# QR_Scanning1_V1_STM32.net
KiCad netlist of a schematic drawn in Altium Designer
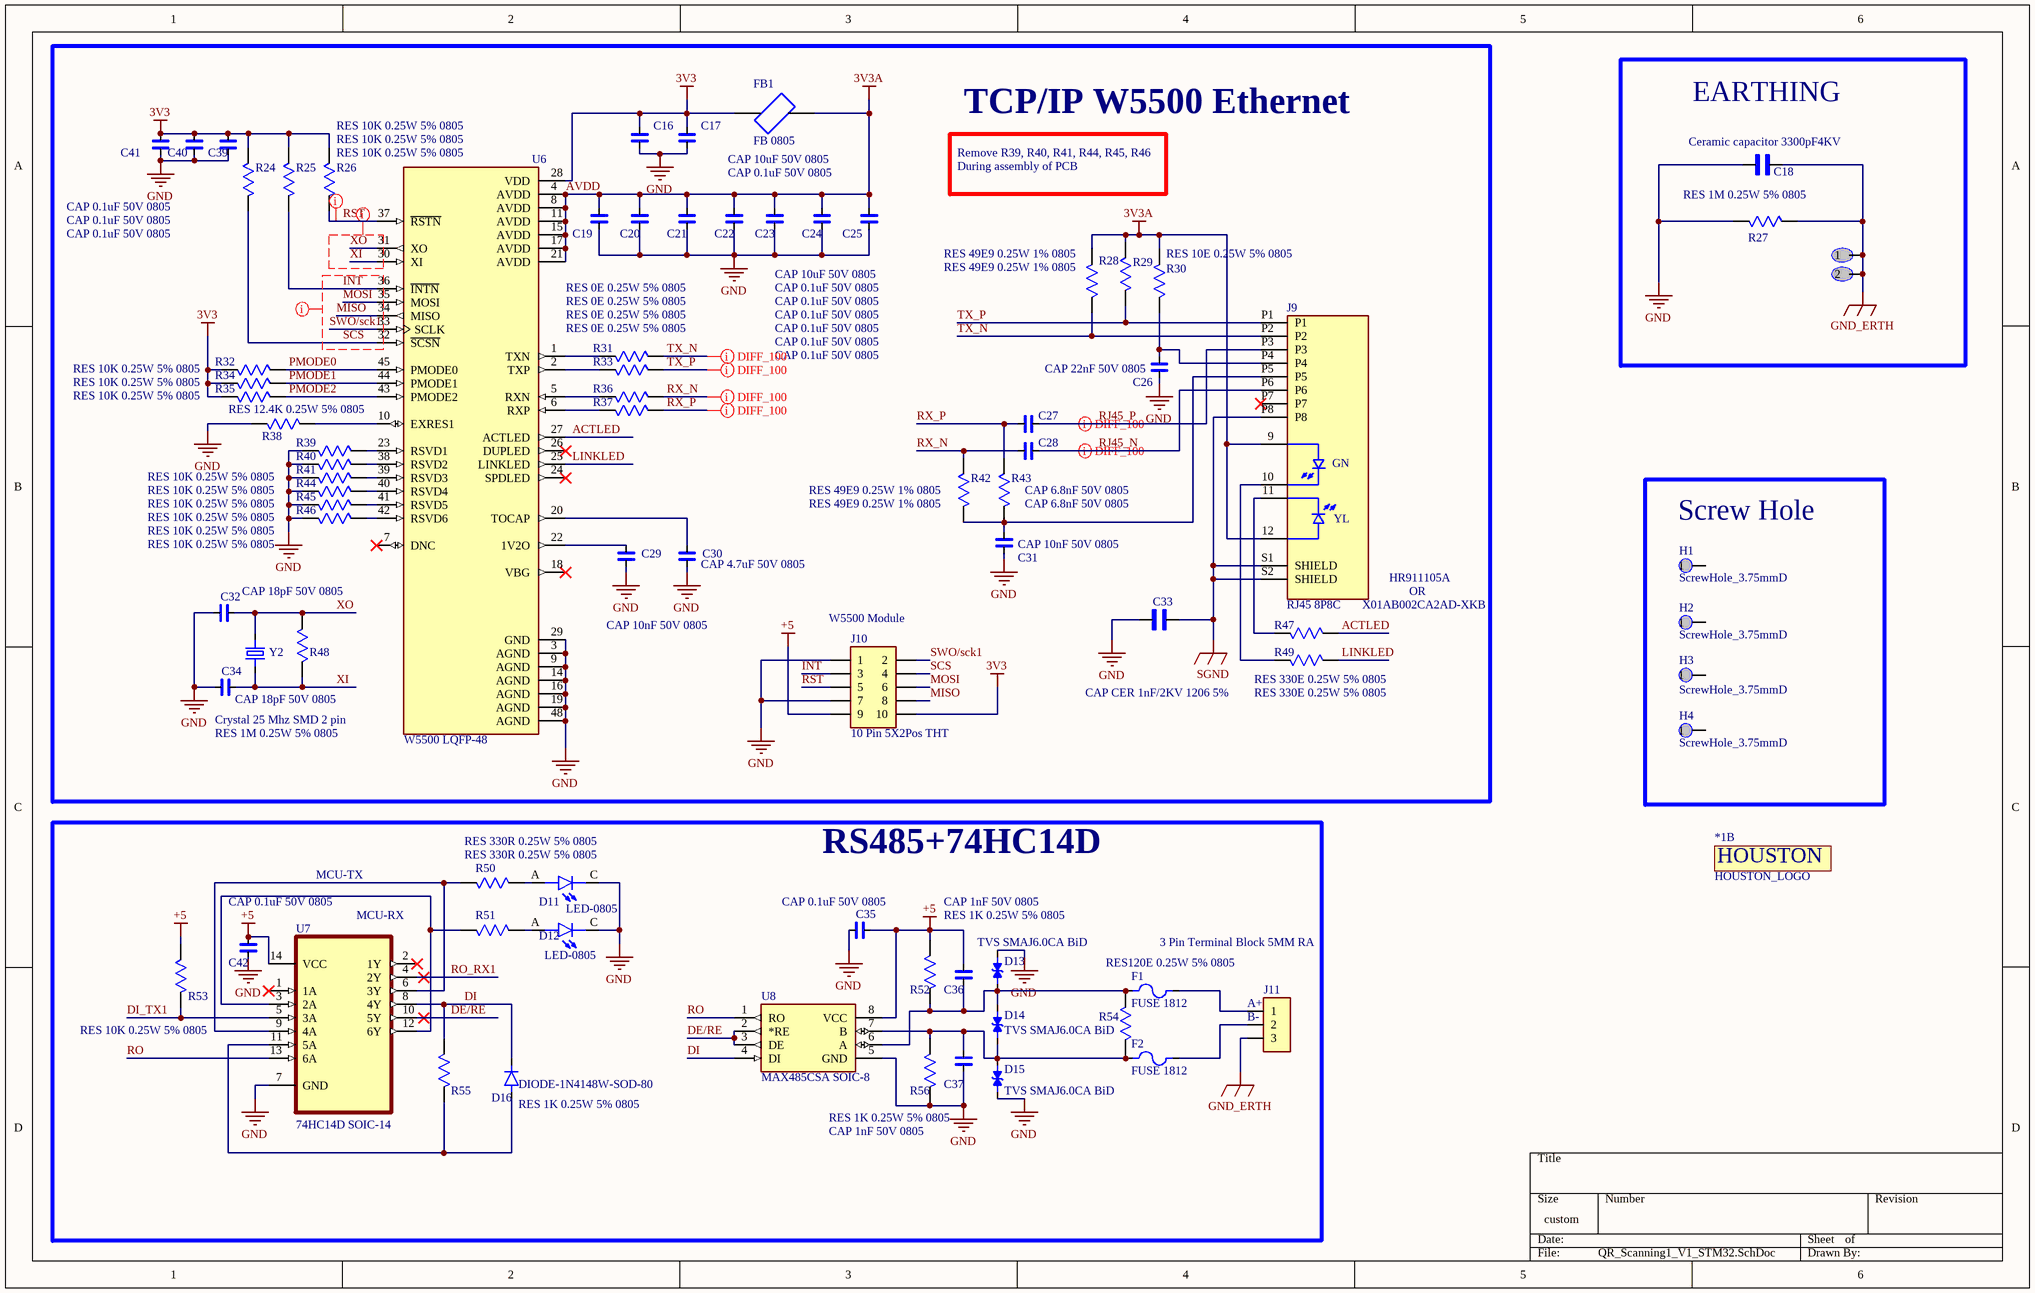
[diagram p0: QR_Scanning1_V1_STM32.SchDoc]

(export (version "E")
  (design (tool "Eeschema 10.0.6"))
  (components
    (comp (ref "*1")
      (value "HOUSTON_LOGO")
      (footprint "HOUSTON_LOGO")
      (libsource (lib "PGS") (part "HOUSTON_LOGO"))
    )
    (comp (ref "C16")
      (value "CAP 0.1uF 50V 0805")
      (footprint "CAP CER 0.1uF/50V 5%")
      (description "CAP CER 0.1uF/50V  Ceramic Capacitor X7R 0805 (2012 Metric) SMT")
      (fields (field (name "MF") "Samsung") (field (name "MP") "CL21B104KCFNNNE"))
      (libsource (lib "Ticket Scanning") (part "CAP CER 0.1uF/50V 5%"))
    )
    (comp (ref "C17")
      (value "CAP 10uF 50V 0805")
      (footprint "CAP CER 0.1uF/50V 5%")
      (description "CAP CER 0.1uF/50V  Ceramic Capacitor X7R 0805 (2012 Metric) SMT")
      (fields (field (name "MF") "Samsung") (field (name "MP") "CL21B104KCFNNNE"))
      (libsource (lib "Ticket Scanning") (part "CAP CER 0.1uF/50V 5%"))
    )
    (comp (ref "C18")
      (value "Ceramic capacitor 3300pF4KV")
      (footprint "Ceramic capacitor 3300pF4KV")
      (description "Ceramic capacitor 3300pF4KV, Tension nominale 400Vac(r.m.s.), 4KV ESD, DE2E3SA332MA3BY02F")
      (fields (field (name "MF") "Murata") (field (name "MP") "DE2E3SA332MA3BY02F"))
      (libsource (lib "Ticket Scanning") (part "Ceramic capacitor 3300pF4KV"))
    )
    (comp (ref "C19")
      (value "CAP 0.1uF 50V 0805")
      (footprint "CAP CER 0.1uF/50V 5%")
      (description "CAP CER 0.1uF/50V  Ceramic Capacitor X7R 0805 (2012 Metric) SMT")
      (fields (field (name "MF") "Samsung") (field (name "MP") "CL21B104KCFNNNE"))
      (libsource (lib "Ticket Scanning") (part "CAP CER 0.1uF/50V 5%"))
    )
    (comp (ref "C20")
      (value "CAP 0.1uF 50V 0805")
      (footprint "CAP CER 0.1uF/50V 5%")
      (description "CAP CER 0.1uF/50V  Ceramic Capacitor X7R 0805 (2012 Metric) SMT")
      (fields (field (name "MF") "Samsung") (field (name "MP") "CL21B104KCFNNNE"))
      (libsource (lib "Ticket Scanning") (part "CAP CER 0.1uF/50V 5%"))
    )
    (comp (ref "C21")
      (value "CAP 0.1uF 50V 0805")
      (footprint "CAP CER 0.1uF/50V 5%")
      (description "CAP CER 0.1uF/50V  Ceramic Capacitor X7R 0805 (2012 Metric) SMT")
      (fields (field (name "MF") "Samsung") (field (name "MP") "CL21B104KCFNNNE"))
      (libsource (lib "Ticket Scanning") (part "CAP CER 0.1uF/50V 5%"))
    )
    (comp (ref "C22")
      (value "CAP 0.1uF 50V 0805")
      (footprint "CAP CER 0.1uF/50V 5%")
      (description "CAP CER 0.1uF/50V  Ceramic Capacitor X7R 0805 (2012 Metric) SMT")
      (fields (field (name "MF") "Samsung") (field (name "MP") "CL21B104KCFNNNE"))
      (libsource (lib "Ticket Scanning") (part "CAP CER 0.1uF/50V 5%"))
    )
    (comp (ref "C23")
      (value "CAP 0.1uF 50V 0805")
      (footprint "CAP CER 0.1uF/50V 5%")
      (description "CAP CER 0.1uF/50V  Ceramic Capacitor X7R 0805 (2012 Metric) SMT")
      (fields (field (name "MF") "Samsung") (field (name "MP") "CL21B104KCFNNNE"))
      (libsource (lib "Ticket Scanning") (part "CAP CER 0.1uF/50V 5%"))
    )
    (comp (ref "C24")
      (value "CAP 0.1uF 50V 0805")
      (footprint "CAP CER 0.1uF/50V 5%")
      (description "CAP CER 0.1uF/50V  Ceramic Capacitor X7R 0805 (2012 Metric) SMT")
      (fields (field (name "MF") "Samsung") (field (name "MP") "CL21B104KCFNNNE"))
      (libsource (lib "Ticket Scanning") (part "CAP CER 0.1uF/50V 5%"))
    )
    (comp (ref "C25")
      (value "CAP 10uF 50V 0805")
      (footprint "CAP CER 0.1uF/50V 5%")
      (description "CAP CER 0.1uF/50V  Ceramic Capacitor X7R 0805 (2012 Metric) SMT")
      (fields (field (name "MF") "Samsung") (field (name "MP") "CL21B104KCFNNNE"))
      (libsource (lib "Ticket Scanning") (part "CAP CER 0.1uF/50V 5%"))
    )
    (comp (ref "C26")
      (value "CAP 22nF 50V 0805")
      (footprint "CAP CER 0.1uF/50V 5%")
      (description "CAP CER 0.1uF/50V  Ceramic Capacitor X7R 0805 (2012 Metric) SMT")
      (fields (field (name "MF") "Samsung") (field (name "MP") "CL21B104KCFNNNE"))
      (libsource (lib "Ticket Scanning") (part "CAP CER 0.1uF/50V 5%"))
    )
    (comp (ref "C27")
      (value "CAP 6.8nF 50V 0805")
      (footprint "CAP CER 0.1uF/50V 5%")
      (description "CAP CER 0.1uF/50V  Ceramic Capacitor X7R 0805 (2012 Metric) SMT")
      (fields (field (name "MF") "Samsung") (field (name "MP") "CL21B104KCFNNNE"))
      (libsource (lib "") (part "CAP CER 0.1uF/50V 5%_1"))
    )
    (comp (ref "C28")
      (value "CAP 6.8nF 50V 0805")
      (footprint "CAP CER 0.1uF/50V 5%")
      (description "CAP CER 0.1uF/50V  Ceramic Capacitor X7R 0805 (2012 Metric) SMT")
      (fields (field (name "MF") "Samsung") (field (name "MP") "CL21B104KCFNNNE"))
      (libsource (lib "") (part "CAP CER 0.1uF/50V 5%_1"))
    )
    (comp (ref "C29")
      (value "CAP 10nF 50V 0805")
      (footprint "CAP CER 0.1uF/50V 5%")
      (description "CAP CER 0.1uF/50V  Ceramic Capacitor X7R 0805 (2012 Metric) SMT")
      (fields (field (name "MF") "Samsung") (field (name "MP") "CL21B104KCFNNNE"))
      (libsource (lib "Ticket Scanning") (part "CAP CER 0.1uF/50V 5%"))
    )
    (comp (ref "C30")
      (value "CAP 4.7uF 50V 0805")
      (footprint "CAP CER 0.1uF/50V 5%")
      (description "CAP CER 0.1uF/50V  Ceramic Capacitor X7R 0805 (2012 Metric) SMT")
      (fields (field (name "MF") "Samsung") (field (name "MP") "CL21B104KCFNNNE"))
      (libsource (lib "Ticket Scanning") (part "CAP CER 0.1uF/50V 5%"))
    )
    (comp (ref "C31")
      (value "CAP 10nF 50V 0805")
      (footprint "CAP CER 0.1uF/50V 5%")
      (description "CAP CER 0.1uF/50V  Ceramic Capacitor X7R 0805 (2012 Metric) SMT")
      (fields (field (name "MF") "Samsung") (field (name "MP") "CL21B104KCFNNNE"))
      (libsource (lib "Ticket Scanning") (part "CAP CER 0.1uF/50V 5%"))
    )
    (comp (ref "C32")
      (value "CAP 18pF 50V 0805")
      (footprint "CAP CER 0.1uF/50V 5%")
      (description "CAP CER 0.1uF/50V  Ceramic Capacitor X7R 0805 (2012 Metric) SMT")
      (fields (field (name "MF") "Samsung") (field (name "MP") "CL21B104KCFNNNE"))
      (libsource (lib "QR_Scanning_STM32") (part "CAP CER 0.1uF/50V 5%"))
    )
    (comp (ref "C33")
      (value "CAP CER 1nF/2KV 1206 5%")
      (footprint "CAP CER 1nF/2KV 1206 5%")
      (description "1000 pF Â±10% 2000V (2kV) Ceramic Capacitor X7R 1206 (3216 Metric) C1206C102KGRACAUTO")
      (fields (field (name "MF") "KEMET") (field (name "MP") "C1206C102KGRACAUTO"))
      (libsource (lib "QR_Scanning_STM32") (part "CAP CER 1nF/2KV 1206 5%"))
    )
    (comp (ref "C34")
      (value "CAP 18pF 50V 0805")
      (footprint "CAP CER 0.1uF/50V 5%")
      (description "CAP CER 0.1uF/50V  Ceramic Capacitor X7R 0805 (2012 Metric) SMT")
      (fields (field (name "MF") "Samsung") (field (name "MP") "CL21B104KCFNNNE"))
      (libsource (lib "QR_Scanning_STM32") (part "CAP CER 0.1uF/50V 5%"))
    )
    (comp (ref "C35")
      (value "CAP 0.1uF 50V 0805")
      (footprint "CAP CER 0.1uF/50V 5%")
      (description "CAP CER 0.1uF/50V  Ceramic Capacitor X7R 0805 (2012 Metric) SMT")
      (fields (field (name "MF") "Samsung") (field (name "MP") "CL21B104KCFNNNE"))
      (libsource (lib "") (part "CAP CER 0.1uF/50V 5%_1"))
    )
    (comp (ref "C36")
      (value "CAP 1nF 50V 0805")
      (footprint "CAP CER 0.1uF/50V 5%")
      (description "CAP CER 0.1uF/50V  Ceramic Capacitor X7R 0805 (2012 Metric) SMT")
      (fields (field (name "MF") "Samsung") (field (name "MP") "CL21B104KCFNNNE"))
      (libsource (lib "Ticket Scanning") (part "CAP CER 0.1uF/50V 5%"))
    )
    (comp (ref "C37")
      (value "CAP 1nF 50V 0805")
      (footprint "CAP CER 0.1uF/50V 5%")
      (description "CAP CER 0.1uF/50V  Ceramic Capacitor X7R 0805 (2012 Metric) SMT")
      (fields (field (name "MF") "Samsung") (field (name "MP") "CL21B104KCFNNNE"))
      (libsource (lib "") (part "CAP CER 0.1uF/50V 5%_2"))
    )
    (comp (ref "C39")
      (value "CAP 0.1uF 50V 0805")
      (footprint "CAP CER 0.1uF/50V 5%")
      (description "CAP CER 0.1uF/50V  Ceramic Capacitor X7R 0805 (2012 Metric) SMT")
      (fields (field (name "MF") "Samsung") (field (name "MP") "CL21B104KCFNNNE"))
      (libsource (lib "Ticket Scanning") (part "CAP CER 0.1uF/50V 5%"))
    )
    (comp (ref "C40")
      (value "CAP 0.1uF 50V 0805")
      (footprint "CAP CER 0.1uF/50V 5%")
      (description "CAP CER 0.1uF/50V  Ceramic Capacitor X7R 0805 (2012 Metric) SMT")
      (fields (field (name "MF") "Samsung") (field (name "MP") "CL21B104KCFNNNE"))
      (libsource (lib "Ticket Scanning") (part "CAP CER 0.1uF/50V 5%"))
    )
    (comp (ref "C41")
      (value "CAP 0.1uF 50V 0805")
      (footprint "CAP CER 0.1uF/50V 5%")
      (description "CAP CER 0.1uF/50V  Ceramic Capacitor X7R 0805 (2012 Metric) SMT")
      (fields (field (name "MF") "Samsung") (field (name "MP") "CL21B104KCFNNNE"))
      (libsource (lib "Ticket Scanning") (part "CAP CER 0.1uF/50V 5%"))
    )
    (comp (ref "C42")
      (value "CAP 0.1uF 50V 0805")
      (footprint "CAP CER 0.1uF/50V 5%")
      (description "CAP CER 0.1uF/50V  Ceramic Capacitor X7R 0805 (2012 Metric) SMT")
      (fields (field (name "MF") "Samsung") (field (name "MP") "CL21B104KCFNNNE"))
      (libsource (lib "Ticket Scanning") (part "CAP CER 0.1uF/50V 5%"))
    )
    (comp (ref "D11")
      (value "LED-0805")
      (footprint "LED-0805")
      (description "Red 640nm LED Indication - Discrete 1.85V 0805 (2012 Metric) APT2012SRCPRV")
      (fields (field (name "MF") "Kingbright") (field (name "MP") "APT2012SRCPRV"))
      (libsource (lib "P10_ESP32") (part "LED-0805"))
    )
    (comp (ref "D12")
      (value "LED-0805")
      (footprint "LED-0805")
      (description "Red 640nm LED Indication - Discrete 1.85V 0805 (2012 Metric) APT2012SRCPRV")
      (fields (field (name "MF") "Kingbright") (field (name "MP") "APT2012SRCPRV"))
      (libsource (lib "P10_ESP32") (part "LED-0805"))
    )
    (comp (ref "D13")
      (value "TVS SMAJ6.0CA BiD")
      (footprint "TVS SMAJ6.0CA DO-214AC (SMA)")
      (description "SMAJ6.0CA WG Bidirectional TVS diode littlefuse DO-214AC (SMA)")
      (fields (field (name "MP") "SMAJ7.5CA"))
      (libsource (lib "QR_Scanning_STM32") (part "TVS SMAJ6.0CA DO-214AC (SMA)"))
    )
    (comp (ref "D14")
      (value "TVS SMAJ6.0CA BiD")
      (footprint "TVS SMAJ6.0CA DO-214AC (SMA)")
      (description "SMAJ6.0CA WG Bidirectional TVS diode littlefuse DO-214AC (SMA)")
      (fields (field (name "MP") "SMAJ7.5CA"))
      (libsource (lib "QR_Scanning_STM32") (part "TVS SMAJ6.0CA DO-214AC (SMA)"))
    )
    (comp (ref "D15")
      (value "TVS SMAJ6.0CA BiD")
      (footprint "TVS SMAJ6.0CA DO-214AC (SMA)")
      (description "SMAJ6.0CA WG Bidirectional TVS diode littlefuse DO-214AC (SMA)")
      (fields (field (name "MP") "SMAJ7.5CA"))
      (libsource (lib "QR_Scanning_STM32") (part "TVS SMAJ6.0CA DO-214AC (SMA)"))
    )
    (comp (ref "D16")
      (value "DIODE-1N4148W-SOD-80")
      (footprint "DIODE-1N4148W-SOD-80")
      (description "DIODE-1N4148W-SOD-80 is a general-purpose silicon diode LL4148_L1G")
      (fields (field (name "MP") "LL4148_L1G"))
      (libsource (lib "QR_Scanning_STM32") (part "DIODE-1N4148W-SOD-80"))
    )
    (comp (ref "EARTHING_VIA HOLE_3.65MM")
      (value "EARTHING_VIA HOLE_3.65MM")
      (footprint "EARTHING_VIA HOLE_3.65MM")
      (libsource (lib "QR_Scanning_STM32") (part "EARTHING_VIA HOLE_3.65MM"))
    )
    (comp (ref "F1")
      (value "FUSE 1812")
      (footprint "FUSE 1812")
      (fields (field (name "MP") "MF-MSMF010-2") (field (name "MF") "Bourns"))
      (libsource (lib "QR_Scanning_STM32") (part "FUSE 1812"))
    )
    (comp (ref "F2")
      (value "FUSE 1812")
      (footprint "FUSE 1812")
      (fields (field (name "MP") "MF-MSMF010-2") (field (name "MF") "Bourns"))
      (libsource (lib "QR_Scanning_STM32") (part "FUSE 1812"))
    )
    (comp (ref "FB1")
      (value "FB 0805")
      (footprint "FB 0805")
      (fields (field (name "MP") "MPZ2012S102AT000"))
      (libsource (lib "QR_Scanning_STM32") (part "FB 0805"))
    )
    (comp (ref "H1")
      (value "ScrewHole_3.75mmD")
      (footprint "ScrewHole_3.75mmD - duplicate")
      (description "SCREW HEAD DIA 4.5MM, SREW LEG DIA 3 MM")
      (libsource (lib "PGS") (part "ScrewHole_3.75mmD"))
    )
    (comp (ref "H2")
      (value "ScrewHole_3.75mmD")
      (footprint "ScrewHole_3.75mmD - duplicate")
      (description "SCREW HEAD DIA 4.5MM, SREW LEG DIA 3 MM")
      (libsource (lib "PGS") (part "ScrewHole_3.75mmD"))
    )
    (comp (ref "H3")
      (value "ScrewHole_3.75mmD")
      (footprint "ScrewHole_3.75mmD - duplicate")
      (description "SCREW HEAD DIA 4.5MM, SREW LEG DIA 3 MM")
      (libsource (lib "PGS") (part "ScrewHole_3.75mmD"))
    )
    (comp (ref "H4")
      (value "ScrewHole_3.75mmD")
      (footprint "ScrewHole_3.75mmD - duplicate")
      (description "SCREW HEAD DIA 4.5MM, SREW LEG DIA 3 MM")
      (libsource (lib "PGS") (part "ScrewHole_3.75mmD"))
    )
    (comp (ref "J9")
      (value "RJ45 8P8C")
      (footprint "RJ45 8P8C")
      (fields (field (name "MF") "Same Sky") (field (name "MP") "CRJ011-ML1-TH"))
      (libsource (lib "QR_Scanning_STM32") (part "RJ45 8P8C"))
    )
    (comp (ref "J10")
      (value "10 Pin 5X2Pos THT")
      (footprint "10 Pin 5X2Pos THT")
      (description "10 Pin 5X2Pos THT BergeStick 2.54MM MTSW-105-X-X-D-X")
      (fields (field (name "MF") "{'manufacturer': u'Samtec Inc.'}") (field (name "MP") "MTSW-105-X-X-D-X"))
      (libsource (lib "QR_Scanning_STM32") (part "10 Pin 5X2Pos THT"))
    )
    (comp (ref "J11")
      (value "3 Pin Terminal Block 5MM RA")
      (footprint "3 Pin Terminal Block 5MM RA")
      (description "3 Pin Terminal Block HDR 5MM THT RA 231-433_001-000")
      (fields (field (name "MP") "231-433/001-000") (field (name "MF") "WAGO"))
      (libsource (lib "QR_Scanning_STM32") (part "3 Pin Terminal Block 5MM RA"))
    )
    (comp (ref "R24")
      (value "RES 10K 0.25W 5% 0805")
      (footprint "RES 0805 10K/0.25W 5%")
      (description "RESISTOR, THICK FILM, 10K, 5%, 0805 0.25W SMT")
      (fields (field (name "MP") "ERJ-6GEYJ103V") (field (name "MF") "Panasonic Electronic"))
      (libsource (lib "QR_Scanning_STM32") (part "RES 10K 0.25W 5% 0805"))
    )
    (comp (ref "R25")
      (value "RES 10K 0.25W 5% 0805")
      (footprint "RES 0805 10K/0.25W 5%")
      (description "RESISTOR, THICK FILM, 10K, 5%, 0805 0.25W SMT")
      (fields (field (name "MP") "ERJ-6GEYJ103V") (field (name "MF") "Panasonic Electronic"))
      (libsource (lib "QR_Scanning_STM32") (part "RES 10K 0.25W 5% 0805"))
    )
    (comp (ref "R26")
      (value "RES 10K 0.25W 5% 0805")
      (footprint "RES 0805 10K/0.25W 5%")
      (description "RESISTOR, THICK FILM, 10K, 5%, 0805 0.25W SMT")
      (fields (field (name "MP") "ERJ-6GEYJ103V") (field (name "MF") "Panasonic Electronic"))
      (libsource (lib "QR_Scanning_STM32") (part "RES 10K 0.25W 5% 0805"))
    )
    (comp (ref "R27")
      (value "RES 1M 0.25W 5% 0805")
      (footprint "RES 0805 10K/0.25W 5%")
      (description "RESISTOR, THICK FILM, 1M, 5%, 0805 0.25W SMT")
      (fields (field (name "MP") "ERJ-6GEYJ103V") (field (name "MF") "Panasonic Electronic"))
      (libsource (lib "Ticket Scanning") (part "RES 10K 0.25W 5% 0805"))
    )
    (comp (ref "R28")
      (value "RES 49E9 0.25W 1% 0805")
      (footprint "RES 0805 10K/0.25W 5%")
      (description "RESISTOR, THICK FILM, 10K, 5%, 0805 0.25W SMT")
      (fields (field (name "MP") "ERJ-6GEYJ103V") (field (name "MF") "Panasonic Electronic"))
      (libsource (lib "QR_Scanning_STM32") (part "RES 10K 0.25W 5% 0805"))
    )
    (comp (ref "R29")
      (value "RES 49E9 0.25W 1% 0805")
      (footprint "RES 0805 10K/0.25W 5%")
      (description "RESISTOR, THICK FILM, 10K, 5%, 0805 0.25W SMT")
      (fields (field (name "MP") "ERJ-6GEYJ103V") (field (name "MF") "Panasonic Electronic"))
      (libsource (lib "QR_Scanning_STM32") (part "RES 10K 0.25W 5% 0805"))
    )
    (comp (ref "R30")
      (value "RES 10E 0.25W 5% 0805")
      (footprint "RES 0805 10K/0.25W 5%")
      (description "RESISTOR, THICK FILM, 10K, 5%, 0805 0.25W SMT")
      (fields (field (name "MP") "ERJ-6GEYJ103V") (field (name "MF") "Panasonic Electronic"))
      (libsource (lib "QR_Scanning_STM32") (part "RES 10K 0.25W 5% 0805"))
    )
    (comp (ref "R31")
      (value "RES 0E 0.25W 5% 0805")
      (footprint "RES 0805 10K/0.25W 5%")
      (description "RESISTOR, THICK FILM, 10K, 5%, 0805 0.25W SMT")
      (fields (field (name "MP") "ERJ-6GEYJ103V") (field (name "MF") "Panasonic Electronic"))
      (libsource (lib "QR_Scanning_STM32") (part "RES 10K 0.25W 5% 0805"))
    )
    (comp (ref "R32")
      (value "RES 10K 0.25W 5% 0805")
      (footprint "RES 0805 10K/0.25W 5%")
      (description "RESISTOR, THICK FILM, 10K, 5%, 0805 0.25W SMT")
      (fields (field (name "MP") "ERJ-6GEYJ103V") (field (name "MF") "Panasonic Electronic"))
      (libsource (lib "QR_Scanning_STM32") (part "RES 10K 0.25W 5% 0805"))
    )
    (comp (ref "R33")
      (value "RES 0E 0.25W 5% 0805")
      (footprint "RES 0805 10K/0.25W 5%")
      (description "RESISTOR, THICK FILM, 10K, 5%, 0805 0.25W SMT")
      (fields (field (name "MP") "ERJ-6GEYJ103V") (field (name "MF") "Panasonic Electronic"))
      (libsource (lib "QR_Scanning_STM32") (part "RES 10K 0.25W 5% 0805"))
    )
    (comp (ref "R34")
      (value "RES 10K 0.25W 5% 0805")
      (footprint "RES 0805 10K/0.25W 5%")
      (description "RESISTOR, THICK FILM, 10K, 5%, 0805 0.25W SMT")
      (fields (field (name "MP") "ERJ-6GEYJ103V") (field (name "MF") "Panasonic Electronic"))
      (libsource (lib "QR_Scanning_STM32") (part "RES 10K 0.25W 5% 0805"))
    )
    (comp (ref "R35")
      (value "RES 10K 0.25W 5% 0805")
      (footprint "RES 0805 10K/0.25W 5%")
      (description "RESISTOR, THICK FILM, 10K, 5%, 0805 0.25W SMT")
      (fields (field (name "MP") "ERJ-6GEYJ103V") (field (name "MF") "Panasonic Electronic"))
      (libsource (lib "QR_Scanning_STM32") (part "RES 10K 0.25W 5% 0805"))
    )
    (comp (ref "R36")
      (value "RES 0E 0.25W 5% 0805")
      (footprint "RES 0805 10K/0.25W 5%")
      (description "RESISTOR, THICK FILM, 10K, 5%, 0805 0.25W SMT")
      (fields (field (name "MP") "ERJ-6GEYJ103V") (field (name "MF") "Panasonic Electronic"))
      (libsource (lib "QR_Scanning_STM32") (part "RES 10K 0.25W 5% 0805"))
    )
    (comp (ref "R37")
      (value "RES 0E 0.25W 5% 0805")
      (footprint "RES 0805 10K/0.25W 5%")
      (description "RESISTOR, THICK FILM, 10K, 5%, 0805 0.25W SMT")
      (fields (field (name "MP") "ERJ-6GEYJ103V") (field (name "MF") "Panasonic Electronic"))
      (libsource (lib "QR_Scanning_STM32") (part "RES 10K 0.25W 5% 0805"))
    )
    (comp (ref "R38")
      (value "RES 12.4K 0.25W 5% 0805")
      (footprint "RES 0805 10K/0.25W 5%")
      (description "RESISTOR, THICK FILM, 10K, 5%, 0805 0.25W SMT")
      (fields (field (name "MP") "ERJ-6GEYJ103V") (field (name "MF") "Panasonic Electronic"))
      (libsource (lib "QR_Scanning_STM32") (part "RES 10K 0.25W 5% 0805"))
    )
    (comp (ref "R39")
      (value "RES 10K 0.25W 5% 0805")
      (footprint "RES 0805 10K/0.25W 5%")
      (description "RESISTOR, THICK FILM, 10K, 5%, 0805 0.25W SMT")
      (fields (field (name "MP") "ERJ-6GEYJ103V") (field (name "MF") "Panasonic Electronic"))
      (libsource (lib "QR_Scanning_STM32") (part "RES 10K 0.25W 5% 0805"))
    )
    (comp (ref "R40")
      (value "RES 10K 0.25W 5% 0805")
      (footprint "RES 0805 10K/0.25W 5%")
      (description "RESISTOR, THICK FILM, 10K, 5%, 0805 0.25W SMT")
      (fields (field (name "MP") "ERJ-6GEYJ103V") (field (name "MF") "Panasonic Electronic"))
      (libsource (lib "QR_Scanning_STM32") (part "RES 10K 0.25W 5% 0805"))
    )
    (comp (ref "R41")
      (value "RES 10K 0.25W 5% 0805")
      (footprint "RES 0805 10K/0.25W 5%")
      (description "RESISTOR, THICK FILM, 10K, 5%, 0805 0.25W SMT")
      (fields (field (name "MP") "ERJ-6GEYJ103V") (field (name "MF") "Panasonic Electronic"))
      (libsource (lib "QR_Scanning_STM32") (part "RES 10K 0.25W 5% 0805"))
    )
    (comp (ref "R42")
      (value "RES 49E9 0.25W 1% 0805")
      (footprint "RES 0805 10K/0.25W 5%")
      (description "RESISTOR, THICK FILM, 10K, 5%, 0805 0.25W SMT")
      (fields (field (name "MP") "ERJ-6GEYJ103V") (field (name "MF") "Panasonic Electronic"))
      (libsource (lib "QR_Scanning_STM32") (part "RES 10K 0.25W 5% 0805"))
    )
    (comp (ref "R43")
      (value "RES 49E9 0.25W 1% 0805")
      (footprint "RES 0805 10K/0.25W 5%")
      (description "RESISTOR, THICK FILM, 10K, 5%, 0805 0.25W SMT")
      (fields (field (name "MP") "ERJ-6GEYJ103V") (field (name "MF") "Panasonic Electronic"))
      (libsource (lib "QR_Scanning_STM32") (part "RES 10K 0.25W 5% 0805"))
    )
    (comp (ref "R44")
      (value "RES 10K 0.25W 5% 0805")
      (footprint "RES 0805 10K/0.25W 5%")
      (description "RESISTOR, THICK FILM, 10K, 5%, 0805 0.25W SMT")
      (fields (field (name "MP") "ERJ-6GEYJ103V") (field (name "MF") "Panasonic Electronic"))
      (libsource (lib "QR_Scanning_STM32") (part "RES 10K 0.25W 5% 0805"))
    )
    (comp (ref "R45")
      (value "RES 10K 0.25W 5% 0805")
      (footprint "RES 0805 10K/0.25W 5%")
      (description "RESISTOR, THICK FILM, 10K, 5%, 0805 0.25W SMT")
      (fields (field (name "MP") "ERJ-6GEYJ103V") (field (name "MF") "Panasonic Electronic"))
      (libsource (lib "QR_Scanning_STM32") (part "RES 10K 0.25W 5% 0805"))
    )
    (comp (ref "R46")
      (value "RES 10K 0.25W 5% 0805")
      (footprint "RES 0805 10K/0.25W 5%")
      (description "RESISTOR, THICK FILM, 10K, 5%, 0805 0.25W SMT")
      (fields (field (name "MP") "ERJ-6GEYJ103V") (field (name "MF") "Panasonic Electronic"))
      (libsource (lib "QR_Scanning_STM32") (part "RES 10K 0.25W 5% 0805"))
    )
    (comp (ref "R47")
      (value "RES 330E 0.25W 5% 0805")
      (footprint "RES 0805 10K/0.25W 5%")
      (description "RESISTOR, THICK FILM, 10K, 5%, 0805 0.25W SMT")
      (fields (field (name "MP") "ERJ-6GEYJ103V") (field (name "MF") "Panasonic Electronic"))
      (libsource (lib "QR_Scanning_STM32") (part "RES 10K 0.25W 5% 0805"))
    )
    (comp (ref "R48")
      (value "RES 1M 0.25W 5% 0805")
      (footprint "RES 0805 10K/0.25W 5%")
      (description "RESISTOR, THICK FILM, 10K, 5%, 0805 0.25W SMT")
      (fields (field (name "MP") "ERJ-6GEYJ103V") (field (name "MF") "Panasonic Electronic"))
      (libsource (lib "QR_Scanning_STM32") (part "RES 10K 0.25W 5% 0805"))
    )
    (comp (ref "R49")
      (value "RES 330E 0.25W 5% 0805")
      (footprint "RES 0805 10K/0.25W 5%")
      (description "RESISTOR, THICK FILM, 10K, 5%, 0805 0.25W SMT")
      (fields (field (name "MP") "ERJ-6GEYJ103V") (field (name "MF") "Panasonic Electronic"))
      (libsource (lib "QR_Scanning_STM32") (part "RES 10K 0.25W 5% 0805"))
    )
    (comp (ref "R50")
      (value "RES 330R 0.25W 5% 0805")
      (footprint "RES 0805 10K/0.25W 5%")
      (description "RESISTOR, THICK FILM, 10K, 5%, 0805 0.25W SMT")
      (fields (field (name "MP") "ERJ-6GEYJ103V") (field (name "MF") "Panasonic Electronic"))
      (libsource (lib "Ticket Scanning") (part "RES 10K 0.25W 5% 0805"))
    )
    (comp (ref "R51")
      (value "RES 330R 0.25W 5% 0805")
      (footprint "RES 0805 10K/0.25W 5%")
      (description "RESISTOR, THICK FILM, 10K, 5%, 0805 0.25W SMT")
      (fields (field (name "MP") "ERJ-6GEYJ103V") (field (name "MF") "Panasonic Electronic"))
      (libsource (lib "Ticket Scanning") (part "RES 10K 0.25W 5% 0805"))
    )
    (comp (ref "R52")
      (value "RES 1K 0.25W 5% 0805")
      (footprint "RES 0805 10K/0.25W 5%")
      (description "RESISTOR, THICK FILM, 10K, 5%, 0805 0.25W SMT")
      (fields (field (name "MP") "ERJ-6GEYJ103V") (field (name "MF") "Panasonic Electronic"))
      (libsource (lib "QR_Scanning_STM32") (part "RES 10K 0.25W 5% 0805"))
    )
    (comp (ref "R53")
      (value "RES 10K 0.25W 5% 0805")
      (footprint "RES 0805 10K/0.25W 5%")
      (description "RESISTOR, THICK FILM, 10K, 5%, 0805 0.25W SMT")
      (fields (field (name "MP") "ERJ-6GEYJ103V") (field (name "MF") "Panasonic Electronic"))
      (libsource (lib "QR_Scanning_STM32") (part "RES 10K 0.25W 5% 0805"))
    )
    (comp (ref "R54")
      (value "RES120E 0.25W 5% 0805")
      (footprint "RES 0805 10K/0.25W 5%")
      (description "RESISTOR, THICK FILM, 10K, 5%, 0805 0.25W SMT")
      (fields (field (name "MP") "ERJ-6GEYJ103V") (field (name "MF") "Panasonic Electronic"))
      (libsource (lib "QR_Scanning_STM32") (part "RES 10K 0.25W 5% 0805"))
    )
    (comp (ref "R55")
      (value "RES 1K 0.25W 5% 0805")
      (footprint "RES 0805 10K/0.25W 5%")
      (description "RESISTOR, THICK FILM, 10K, 5%, 0805 0.25W SMT")
      (fields (field (name "MP") "ERJ-6GEYJ103V") (field (name "MF") "Panasonic Electronic"))
      (libsource (lib "QR_Scanning_STM32") (part "RES 10K 0.25W 5% 0805"))
    )
    (comp (ref "R56")
      (value "RES 1K 0.25W 5% 0805")
      (footprint "RES 0805 10K/0.25W 5%")
      (description "RESISTOR, THICK FILM, 10K, 5%, 0805 0.25W SMT")
      (fields (field (name "MP") "ERJ-6GEYJ103V") (field (name "MF") "Panasonic Electronic"))
      (libsource (lib "QR_Scanning_STM32") (part "RES 10K 0.25W 5% 0805"))
    )
    (comp (ref "U6")
      (value "W5500 LQFP-48")
      (footprint "W5500 LQFP-48")
      (description "W5500 LQFP-48 Hardwired TCP/IP embedded Ethernet controller")
      (fields (field (name "MP") "W5500"))
      (libsource (lib "QR_Scanning_STM32") (part "W5500"))
    )
    (comp (ref "U7")
      (value "74HC14D SOIC-14")
      (footprint "74HC14D SOIC-14")
      (description "Inverter IC 6 Channel Schmitt Trigger 14-SO/SOIC-14")
      (fields (field (name "MF") "Nexperia USA") (field (name "MP") "74HC14D,653"))
      (libsource (lib "QR_Scanning_STM32") (part "74HC14D,653"))
    )
    (comp (ref "U8")
      (value "MAX485CSA SOIC-8")
      (footprint "MAX485CSA")
      (description "MAX485CSA-RS-485/RS-422 Transceivers, SOIC-8")
      (fields (field (name "MF") "Analog Devices") (field (name "MP") "MAX485CSA+"))
      (libsource (lib "QR_Scanning_STM32") (part "MAX485CSA"))
    )
    (comp (ref "Y2")
      (value "Crystal 25 Mhz SMD 2 pin")
      (footprint "Crystal 16 Mhz SMD 2 pin")
      (fields (field (name "MF") "Fox Electronics") (field (name "MP") "FOXSDLF/128-20"))
      (libsource (lib "QR_Scanning_STM32") (part "Crystal 16 Mhz SMD 2 pin_1"))
    )
  )
  (nets
    (net (code "1") (name "+5") (class "Default")
      (node (ref "C35") (pin "1") (pinfunction "1_1") (pintype "passive"))
      (node (ref "C36") (pin "2") (pinfunction "2_2") (pintype "passive"))
      (node (ref "C42") (pin "2") (pinfunction "2_2") (pintype "passive"))
      (node (ref "J10") (pin "9") (pinfunction "9_9") (pintype "passive"))
      (node (ref "R52") (pin "1") (pinfunction "1_1") (pintype "passive"))
      (node (ref "R53") (pin "2") (pinfunction "2_2") (pintype "passive"))
      (node (ref "U7") (pin "14") (pinfunction "VCC_14") (pintype "power_in"))
      (node (ref "U8") (pin "8") (pinfunction "VCC_8") (pintype "power_in"))
    )
    (net (code "2") (name "/ACTLED") (class "Default")
      (node (ref "R47") (pin "1") (pinfunction "1_1") (pintype "passive"))
      (node (ref "U6") (pin "27") (pinfunction "ACTLED_27") (pintype "output"))
    )
    (net (code "3") (name "/DE{slash}RE") (class "Default")
      (node (ref "U7") (pin "10") (pinfunction "5Y_10") (pintype "output"))
      (node (ref "U8") (pin "2") (pinfunction "*RE_2") (pintype "output"))
      (node (ref "U8") (pin "3") (pinfunction "DE_3") (pintype "output"))
    )
    (net (code "4") (name "/DI") (class "Default")
      (node (ref "D16") (pin "C") (pinfunction "K_C") (pintype "passive"))
      (node (ref "R55") (pin "2") (pinfunction "2_2") (pintype "passive"))
      (node (ref "U7") (pin "8") (pinfunction "4Y_8") (pintype "output"))
      (node (ref "U8") (pin "4") (pinfunction "DI_4") (pintype "input"))
    )
    (net (code "5") (name "/DI_TX1") (class "Default")
      (node (ref "R53") (pin "1") (pinfunction "1_1") (pintype "passive"))
      (node (ref "U7") (pin "5") (pinfunction "3A_5") (pintype "input"))
    )
    (net (code "6") (name "/INT") (class "Default")
      (node (ref "J10") (pin "3") (pinfunction "3_3") (pintype "passive"))
      (node (ref "R25") (pin "1") (pinfunction "1_1") (pintype "passive"))
      (node (ref "U6") (pin "36") (pinfunction "~{INTN}_36") (pintype "input"))
    )
    (net (code "7") (name "/LINKLED") (class "Default")
      (node (ref "R49") (pin "1") (pinfunction "1_1") (pintype "passive"))
      (node (ref "U6") (pin "25") (pinfunction "LINKLED_25") (pintype "output"))
    )
    (net (code "8") (name "/MISO") (class "Default")
      (node (ref "J10") (pin "8") (pinfunction "8_8") (pintype "passive"))
      (node (ref "U6") (pin "34") (pinfunction "MISO_34") (pintype "output"))
    )
    (net (code "9") (name "/MOSI") (class "Default")
      (node (ref "J10") (pin "6") (pinfunction "6_6") (pintype "passive"))
      (node (ref "U6") (pin "35") (pinfunction "MOSI_35") (pintype "input"))
    )
    (net (code "10") (name "/PMODE0") (class "Default")
      (node (ref "R32") (pin "1") (pinfunction "1_1") (pintype "passive"))
      (node (ref "U6") (pin "45") (pinfunction "PMODE0_45") (pintype "input"))
    )
    (net (code "11") (name "/PMODE1") (class "Default")
      (node (ref "R34") (pin "1") (pinfunction "1_1") (pintype "passive"))
      (node (ref "U6") (pin "44") (pinfunction "PMODE1_44") (pintype "input"))
    )
    (net (code "12") (name "/PMODE2") (class "Default")
      (node (ref "R35") (pin "1") (pinfunction "1_1") (pintype "passive"))
      (node (ref "U6") (pin "43") (pinfunction "PMODE2_43") (pintype "input"))
    )
    (net (code "13") (name "/RJ45_N") (class "Default")
      (node (ref "C28") (pin "1") (pinfunction "1_1") (pintype "passive"))
      (node (ref "J9") (pin "P6") (pinfunction "P6_P6") (pintype "passive"))
    )
    (net (code "14") (name "/RJ45_P") (class "Default")
      (node (ref "C27") (pin "1") (pinfunction "1_1") (pintype "passive"))
      (node (ref "J9") (pin "P3") (pinfunction "P3_P3") (pintype "passive"))
    )
    (net (code "15") (name "/RO") (class "Default")
      (node (ref "U7") (pin "13") (pinfunction "6A_13") (pintype "input"))
      (node (ref "U8") (pin "1") (pinfunction "RO_1") (pintype "output"))
    )
    (net (code "16") (name "/RO_RX1") (class "Default")
      (node (ref "U7") (pin "4") (pinfunction "2Y_4") (pintype "output"))
    )
    (net (code "17") (name "/RST") (class "Default")
      (node (ref "J10") (pin "5") (pinfunction "5_5") (pintype "passive"))
      (node (ref "R26") (pin "1") (pinfunction "1_1") (pintype "passive"))
      (node (ref "U6") (pin "37") (pinfunction "~{RSTN}_37") (pintype "input"))
    )
    (net (code "18") (name "/RX_N") (class "Default")
      (node (ref "C28") (pin "2") (pinfunction "2_2") (pintype "passive"))
      (node (ref "R36") (pin "1") (pinfunction "1_1") (pintype "passive"))
      (node (ref "R42") (pin "2") (pinfunction "2_2") (pintype "passive"))
    )
    (net (code "19") (name "/RX_P") (class "Default")
      (node (ref "C27") (pin "2") (pinfunction "2_2") (pintype "passive"))
      (node (ref "R37") (pin "1") (pinfunction "1_1") (pintype "passive"))
      (node (ref "R43") (pin "2") (pinfunction "2_2") (pintype "passive"))
    )
    (net (code "20") (name "/SCS") (class "Default")
      (node (ref "J10") (pin "4") (pinfunction "4_4") (pintype "passive"))
      (node (ref "R24") (pin "1") (pinfunction "1_1") (pintype "passive"))
      (node (ref "U6") (pin "32") (pinfunction "~{SCSN}_32") (pintype "input"))
    )
    (net (code "21") (name "/SWO{slash}sck1") (class "Default")
      (node (ref "J10") (pin "2") (pinfunction "2_2") (pintype "passive"))
      (node (ref "U6") (pin "33") (pinfunction "SCLK_33") (pintype "input"))
    )
    (net (code "22") (name "/TX_N") (class "Default")
      (node (ref "J9") (pin "P2") (pinfunction "P2_P2") (pintype "passive"))
      (node (ref "R28") (pin "1") (pinfunction "1_1") (pintype "passive"))
      (node (ref "R31") (pin "1") (pinfunction "1_1") (pintype "passive"))
    )
    (net (code "23") (name "/TX_P") (class "Default")
      (node (ref "J9") (pin "P1") (pinfunction "P1_P1") (pintype "passive"))
      (node (ref "R29") (pin "1") (pinfunction "1_1") (pintype "passive"))
      (node (ref "R33") (pin "1") (pinfunction "1_1") (pintype "passive"))
    )
    (net (code "24") (name "/XI") (class "Default")
      (node (ref "C34") (pin "1") (pinfunction "1_1") (pintype "passive"))
      (node (ref "R48") (pin "1") (pinfunction "1_1") (pintype "passive"))
      (node (ref "U6") (pin "30") (pinfunction "XI_30") (pintype "input"))
      (node (ref "Y2") (pin "2") (pinfunction "2_2") (pintype "passive"))
    )
    (net (code "25") (name "/XO") (class "Default")
      (node (ref "C32") (pin "1") (pinfunction "1_1") (pintype "passive"))
      (node (ref "R48") (pin "2") (pinfunction "2_2") (pintype "passive"))
      (node (ref "U6") (pin "31") (pinfunction "XO_31") (pintype "output"))
      (node (ref "Y2") (pin "1") (pinfunction "1_1") (pintype "passive"))
    )
    (net (code "26") (name "3V3") (class "Default")
      (node (ref "C16") (pin "2") (pinfunction "2_2") (pintype "passive"))
      (node (ref "C17") (pin "2") (pinfunction "2_2") (pintype "passive"))
      (node (ref "C39") (pin "2") (pinfunction "2_2") (pintype "passive"))
      (node (ref "C40") (pin "2") (pinfunction "2_2") (pintype "passive"))
      (node (ref "C41") (pin "2") (pinfunction "2_2") (pintype "passive"))
      (node (ref "FB1") (pin "1") (pinfunction "1_1") (pintype "passive"))
      (node (ref "J10") (pin "10") (pinfunction "10_10") (pintype "passive"))
      (node (ref "R24") (pin "2") (pinfunction "2_2") (pintype "passive"))
      (node (ref "R25") (pin "2") (pinfunction "2_2") (pintype "passive"))
      (node (ref "R26") (pin "2") (pinfunction "2_2") (pintype "passive"))
      (node (ref "R32") (pin "2") (pinfunction "2_2") (pintype "passive"))
      (node (ref "R34") (pin "2") (pinfunction "2_2") (pintype "passive"))
      (node (ref "R35") (pin "2") (pinfunction "2_2") (pintype "passive"))
      (node (ref "U6") (pin "28") (pinfunction "VDD_28") (pintype "power_in"))
    )
    (net (code "27") (name "3V3A") (class "Default")
      (node (ref "C19") (pin "2") (pinfunction "2_2") (pintype "passive"))
      (node (ref "C20") (pin "2") (pinfunction "2_2") (pintype "passive"))
      (node (ref "C21") (pin "2") (pinfunction "2_2") (pintype "passive"))
      (node (ref "C22") (pin "2") (pinfunction "2_2") (pintype "passive"))
      (node (ref "C23") (pin "2") (pinfunction "2_2") (pintype "passive"))
      (node (ref "C24") (pin "2") (pinfunction "2_2") (pintype "passive"))
      (node (ref "C25") (pin "2") (pinfunction "2_2") (pintype "passive"))
      (node (ref "FB1") (pin "2") (pinfunction "2_2") (pintype "passive"))
      (node (ref "J9") (pin "12") (pinfunction "12_12") (pintype "passive"))
      (node (ref "J9") (pin "9") (pinfunction "9_9") (pintype "passive"))
      (node (ref "R28") (pin "2") (pinfunction "2_2") (pintype "passive"))
      (node (ref "R29") (pin "2") (pinfunction "2_2") (pintype "passive"))
      (node (ref "R30") (pin "2") (pinfunction "2_2") (pintype "passive"))
      (node (ref "U6") (pin "11") (pinfunction "AVDD_11") (pintype "power_in"))
      (node (ref "U6") (pin "15") (pinfunction "AVDD_15") (pintype "power_in"))
      (node (ref "U6") (pin "17") (pinfunction "AVDD_17") (pintype "power_in"))
      (node (ref "U6") (pin "21") (pinfunction "AVDD_21") (pintype "power_in"))
      (node (ref "U6") (pin "4") (pinfunction "AVDD_4") (pintype "power_in"))
      (node (ref "U6") (pin "8") (pinfunction "AVDD_8") (pintype "power_in"))
    )
    (net (code "28") (name "GND") (class "Default")
      (node (ref "C16") (pin "1") (pinfunction "1_1") (pintype "passive"))
      (node (ref "C17") (pin "1") (pinfunction "1_1") (pintype "passive"))
      (node (ref "C18") (pin "1") (pinfunction "1_1") (pintype "passive"))
      (node (ref "C19") (pin "1") (pinfunction "1_1") (pintype "passive"))
      (node (ref "C20") (pin "1") (pinfunction "1_1") (pintype "passive"))
      (node (ref "C21") (pin "1") (pinfunction "1_1") (pintype "passive"))
      (node (ref "C22") (pin "1") (pinfunction "1_1") (pintype "passive"))
      (node (ref "C23") (pin "1") (pinfunction "1_1") (pintype "passive"))
      (node (ref "C24") (pin "1") (pinfunction "1_1") (pintype "passive"))
      (node (ref "C25") (pin "1") (pinfunction "1_1") (pintype "passive"))
      (node (ref "C26") (pin "1") (pinfunction "1_1") (pintype "passive"))
      (node (ref "C29") (pin "1") (pinfunction "1_1") (pintype "passive"))
      (node (ref "C30") (pin "1") (pinfunction "1_1") (pintype "passive"))
      (node (ref "C31") (pin "1") (pinfunction "1_1") (pintype "passive"))
      (node (ref "C32") (pin "2") (pinfunction "2_2") (pintype "passive"))
      (node (ref "C33") (pin "1") (pinfunction "1_1") (pintype "passive"))
      (node (ref "C34") (pin "2") (pinfunction "2_2") (pintype "passive"))
      (node (ref "C35") (pin "2") (pinfunction "2_2") (pintype "passive"))
      (node (ref "C37") (pin "2") (pinfunction "2_2") (pintype "passive"))
      (node (ref "C39") (pin "1") (pinfunction "1_1") (pintype "passive"))
      (node (ref "C40") (pin "1") (pinfunction "1_1") (pintype "passive"))
      (node (ref "C41") (pin "1") (pinfunction "1_1") (pintype "passive"))
      (node (ref "C42") (pin "1") (pinfunction "1_1") (pintype "passive"))
      (node (ref "D11") (pin "C") (pinfunction "C_C") (pintype "passive"))
      (node (ref "D12") (pin "C") (pinfunction "C_C") (pintype "passive"))
      (node (ref "D13") (pin "2") (pinfunction "2_2") (pintype "passive"))
      (node (ref "D15") (pin "1") (pinfunction "1_1") (pintype "passive"))
      (node (ref "J10") (pin "1") (pinfunction "1_1") (pintype "passive"))
      (node (ref "J10") (pin "7") (pinfunction "7_7") (pintype "passive"))
      (node (ref "R27") (pin "1") (pinfunction "1_1") (pintype "passive"))
      (node (ref "R38") (pin "1") (pinfunction "1_1") (pintype "passive"))
      (node (ref "R39") (pin "2") (pinfunction "2_2") (pintype "passive"))
      (node (ref "R40") (pin "2") (pinfunction "2_2") (pintype "passive"))
      (node (ref "R41") (pin "2") (pinfunction "2_2") (pintype "passive"))
      (node (ref "R44") (pin "2") (pinfunction "2_2") (pintype "passive"))
      (node (ref "R45") (pin "2") (pinfunction "2_2") (pintype "passive"))
      (node (ref "R46") (pin "2") (pinfunction "2_2") (pintype "passive"))
      (node (ref "R56") (pin "1") (pinfunction "1_1") (pintype "passive"))
      (node (ref "U6") (pin "14") (pinfunction "AGND_14") (pintype "power_in"))
      (node (ref "U6") (pin "16") (pinfunction "AGND_16") (pintype "power_in"))
      (node (ref "U6") (pin "19") (pinfunction "AGND_19") (pintype "power_in"))
      (node (ref "U6") (pin "29") (pinfunction "GND_29") (pintype "passive"))
      (node (ref "U6") (pin "3") (pinfunction "AGND_3") (pintype "power_in"))
      (node (ref "U6") (pin "48") (pinfunction "AGND_48") (pintype "power_in"))
      (node (ref "U6") (pin "9") (pinfunction "AGND_9") (pintype "power_in"))
      (node (ref "U7") (pin "7") (pinfunction "GND_7") (pintype "passive"))
      (node (ref "U8") (pin "5") (pinfunction "GND_5") (pintype "power_in"))
    )
    (net (code "29") (name "GND_ERTH") (class "Default")
      (node (ref "C18") (pin "2") (pinfunction "2_2") (pintype "passive"))
      (node (ref "EARTHING_VIA HOLE_3.65MM") (pin "1") (pinfunction "1_1") (pintype "passive"))
      (node (ref "EARTHING_VIA HOLE_3.65MM") (pin "2") (pinfunction "2_2") (pintype "passive"))
      (node (ref "J11") (pin "3") (pinfunction "3_3") (pintype "passive"))
      (node (ref "R27") (pin "2") (pinfunction "2_2") (pintype "passive"))
    )
    (net (code "30") (name "Net-(C26-Pad2)") (class "Default")
      (node (ref "C26") (pin "2") (pinfunction "2_2") (pintype "passive"))
      (node (ref "J9") (pin "P4") (pinfunction "P4_P4") (pintype "passive"))
      (node (ref "R30") (pin "1") (pinfunction "1_1") (pintype "passive"))
    )
    (net (code "31") (name "Net-(C31-Pad2)") (class "Default")
      (node (ref "C31") (pin "2") (pinfunction "2_2") (pintype "passive"))
      (node (ref "J9") (pin "P5") (pinfunction "P5_P5") (pintype "passive"))
      (node (ref "R42") (pin "1") (pinfunction "1_1") (pintype "passive"))
      (node (ref "R43") (pin "1") (pinfunction "1_1") (pintype "passive"))
    )
    (net (code "32") (name "Net-(D11-PadA)") (class "Default")
      (node (ref "D11") (pin "A") (pinfunction "A_A") (pintype "passive"))
      (node (ref "R50") (pin "1") (pinfunction "1_1") (pintype "passive"))
    )
    (net (code "33") (name "Net-(D12-PadA)") (class "Default")
      (node (ref "D12") (pin "A") (pinfunction "A_A") (pintype "passive"))
      (node (ref "R51") (pin "1") (pinfunction "1_1") (pintype "passive"))
    )
    (net (code "34") (name "Net-(F1-Pad2)") (class "Default")
      (node (ref "F1") (pin "2") (pinfunction "2_2") (pintype "passive"))
      (node (ref "J11") (pin "1") (pinfunction "1_1") (pintype "passive"))
    )
    (net (code "35") (name "Net-(F2-Pad2)") (class "Default")
      (node (ref "F2") (pin "2") (pinfunction "2_2") (pintype "passive"))
      (node (ref "J11") (pin "2") (pinfunction "2_2") (pintype "passive"))
    )
    (net (code "36") (name "Net-(J9-Pad10)") (class "Default")
      (node (ref "J9") (pin "10") (pinfunction "10_10") (pintype "passive"))
      (node (ref "R49") (pin "2") (pinfunction "2_2") (pintype "passive"))
    )
    (net (code "37") (name "Net-(J9-Pad11)") (class "Default")
      (node (ref "J9") (pin "11") (pinfunction "11_11") (pintype "passive"))
      (node (ref "R47") (pin "2") (pinfunction "2_2") (pintype "passive"))
    )
    (net (code "38") (name "Net-(U6-1V2O)") (class "Default")
      (node (ref "C29") (pin "2") (pinfunction "2_2") (pintype "passive"))
      (node (ref "U6") (pin "22") (pinfunction "1V2O_22") (pintype "output"))
    )
    (net (code "39") (name "Net-(U6-EXRES1)") (class "Default")
      (node (ref "R38") (pin "2") (pinfunction "2_2") (pintype "passive"))
      (node (ref "U6") (pin "10") (pinfunction "EXRES1_10") (pintype "bidirectional"))
    )
    (net (code "40") (name "Net-(U6-RSVD1)") (class "Default")
      (node (ref "R39") (pin "1") (pinfunction "1_1") (pintype "passive"))
      (node (ref "U6") (pin "23") (pinfunction "RSVD1_23") (pintype "input"))
    )
    (net (code "41") (name "Net-(U6-RSVD2)") (class "Default")
      (node (ref "R40") (pin "1") (pinfunction "1_1") (pintype "passive"))
      (node (ref "U6") (pin "38") (pinfunction "RSVD2_38") (pintype "input"))
    )
    (net (code "42") (name "Net-(U6-RSVD3)") (class "Default")
      (node (ref "R41") (pin "1") (pinfunction "1_1") (pintype "passive"))
      (node (ref "U6") (pin "39") (pinfunction "RSVD3_39") (pintype "input"))
    )
    (net (code "43") (name "Net-(U6-RSVD4)") (class "Default")
      (node (ref "R44") (pin "1") (pinfunction "1_1") (pintype "passive"))
      (node (ref "U6") (pin "40") (pinfunction "RSVD4_40") (pintype "input"))
    )
    (net (code "44") (name "Net-(U6-RSVD5)") (class "Default")
      (node (ref "R45") (pin "1") (pinfunction "1_1") (pintype "passive"))
      (node (ref "U6") (pin "41") (pinfunction "RSVD5_41") (pintype "input"))
    )
    (net (code "45") (name "Net-(U6-RSVD6)") (class "Default")
      (node (ref "R46") (pin "1") (pinfunction "1_1") (pintype "passive"))
      (node (ref "U6") (pin "42") (pinfunction "RSVD6_42") (pintype "input"))
    )
    (net (code "46") (name "Net-(U6-RXN)") (class "Default")
      (node (ref "R36") (pin "2") (pinfunction "2_2") (pintype "passive"))
      (node (ref "U6") (pin "5") (pinfunction "RXN_5") (pintype "input"))
    )
    (net (code "47") (name "Net-(U6-RXP)") (class "Default")
      (node (ref "R37") (pin "2") (pinfunction "2_2") (pintype "passive"))
      (node (ref "U6") (pin "6") (pinfunction "RXP_6") (pintype "input"))
    )
    (net (code "48") (name "Net-(U6-TOCAP)") (class "Default")
      (node (ref "C30") (pin "2") (pinfunction "2_2") (pintype "passive"))
      (node (ref "U6") (pin "20") (pinfunction "TOCAP_20") (pintype "output"))
    )
    (net (code "49") (name "Net-(U6-TXN)") (class "Default")
      (node (ref "R31") (pin "2") (pinfunction "2_2") (pintype "passive"))
      (node (ref "U6") (pin "1") (pinfunction "TXN_1") (pintype "output"))
    )
    (net (code "50") (name "Net-(U6-TXP)") (class "Default")
      (node (ref "R33") (pin "2") (pinfunction "2_2") (pintype "passive"))
      (node (ref "U6") (pin "2") (pinfunction "TXP_2") (pintype "output"))
    )
    (net (code "51") (name "Net-(U7-2A)") (class "Default")
      (node (ref "R51") (pin "2") (pinfunction "2_2") (pintype "passive"))
      (node (ref "U7") (pin "12") (pinfunction "6Y_12") (pintype "output"))
      (node (ref "U7") (pin "3") (pinfunction "2A_3") (pintype "input"))
    )
    (net (code "52") (name "Net-(U7-3Y)") (class "Default")
      (node (ref "R50") (pin "2") (pinfunction "2_2") (pintype "passive"))
      (node (ref "U7") (pin "6") (pinfunction "3Y_6") (pintype "output"))
      (node (ref "U7") (pin "9") (pinfunction "4A_9") (pintype "input"))
    )
    (net (code "53") (name "Net-(U7-5A)") (class "Default")
      (node (ref "D16") (pin "A") (pinfunction "A_A") (pintype "passive"))
      (node (ref "R55") (pin "1") (pinfunction "1_1") (pintype "passive"))
      (node (ref "U7") (pin "11") (pinfunction "5A_11") (pintype "input"))
    )
    (net (code "54") (name "Net-(U8-A)") (class "Default")
      (node (ref "C36") (pin "1") (pinfunction "1_1") (pintype "passive"))
      (node (ref "D13") (pin "1") (pinfunction "1_1") (pintype "passive"))
      (node (ref "D14") (pin "2") (pinfunction "2_2") (pintype "passive"))
      (node (ref "F1") (pin "1") (pinfunction "1_1") (pintype "passive"))
      (node (ref "R52") (pin "2") (pinfunction "2_2") (pintype "passive"))
      (node (ref "R54") (pin "2") (pinfunction "2_2") (pintype "passive"))
      (node (ref "U8") (pin "6") (pinfunction "A_6") (pintype "bidirectional"))
    )
    (net (code "55") (name "Net-(U8-B)") (class "Default")
      (node (ref "C37") (pin "1") (pinfunction "1_1") (pintype "passive"))
      (node (ref "D14") (pin "1") (pinfunction "1_1") (pintype "passive"))
      (node (ref "D15") (pin "2") (pinfunction "2_2") (pintype "passive"))
      (node (ref "F2") (pin "1") (pinfunction "1_1") (pintype "passive"))
      (node (ref "R54") (pin "1") (pinfunction "1_1") (pintype "passive"))
      (node (ref "R56") (pin "2") (pinfunction "2_2") (pintype "passive"))
      (node (ref "U8") (pin "7") (pinfunction "B_7") (pintype "bidirectional"))
    )
    (net (code "56") (name "SGND") (class "Default")
      (node (ref "C33") (pin "2") (pinfunction "2_2") (pintype "passive"))
      (node (ref "J9") (pin "P8") (pinfunction "P8_P8") (pintype "passive"))
      (node (ref "J9") (pin "S1") (pinfunction "SHIELD_S1") (pintype "passive"))
      (node (ref "J9") (pin "S2") (pinfunction "SHIELD_S2") (pintype "passive"))
    )
    (net (code "57") (name "unconnected-(H1-Pad1)") (class "Default")
      (node (ref "H1") (pin "1") (pinfunction "1_1") (pintype "passive"))
    )
    (net (code "58") (name "unconnected-(H2-Pad1)") (class "Default")
      (node (ref "H2") (pin "1") (pinfunction "1_1") (pintype "passive"))
    )
    (net (code "59") (name "unconnected-(H3-Pad1)") (class "Default")
      (node (ref "H3") (pin "1") (pinfunction "1_1") (pintype "passive"))
    )
    (net (code "60") (name "unconnected-(H4-Pad1)") (class "Default")
      (node (ref "H4") (pin "1") (pinfunction "1_1") (pintype "passive"))
    )
    (net (code "61") (name "unconnected-(J9-PadP7)") (class "Default")
      (node (ref "J9") (pin "P7") (pinfunction "P7_P7") (pintype "passive+no_connect"))
    )
    (net (code "62") (name "unconnected-(U6-DNC-Pad7)") (class "Default")
      (node (ref "U6") (pin "7") (pinfunction "DNC_7") (pintype "bidirectional+no_connect"))
    )
    (net (code "63") (name "unconnected-(U6-DUPLED-Pad26)") (class "Default")
      (node (ref "U6") (pin "26") (pinfunction "DUPLED_26") (pintype "output+no_connect"))
    )
    (net (code "64") (name "unconnected-(U6-SPDLED-Pad24)") (class "Default")
      (node (ref "U6") (pin "24") (pinfunction "SPDLED_24") (pintype "output+no_connect"))
    )
    (net (code "65") (name "unconnected-(U6-VBG-Pad18)") (class "Default")
      (node (ref "U6") (pin "18") (pinfunction "VBG_18") (pintype "output+no_connect"))
    )
    (net (code "66") (name "unconnected-(U7-1A-Pad1)") (class "Default")
      (node (ref "U7") (pin "1") (pinfunction "1A_1") (pintype "input+no_connect"))
    )
    (net (code "67") (name "unconnected-(U7-1Y-Pad2)") (class "Default")
      (node (ref "U7") (pin "2") (pinfunction "1Y_2") (pintype "output+no_connect"))
    )
  )
)
